# Rev1.net
KiCad netlist of a schematic drawn in EAGLE
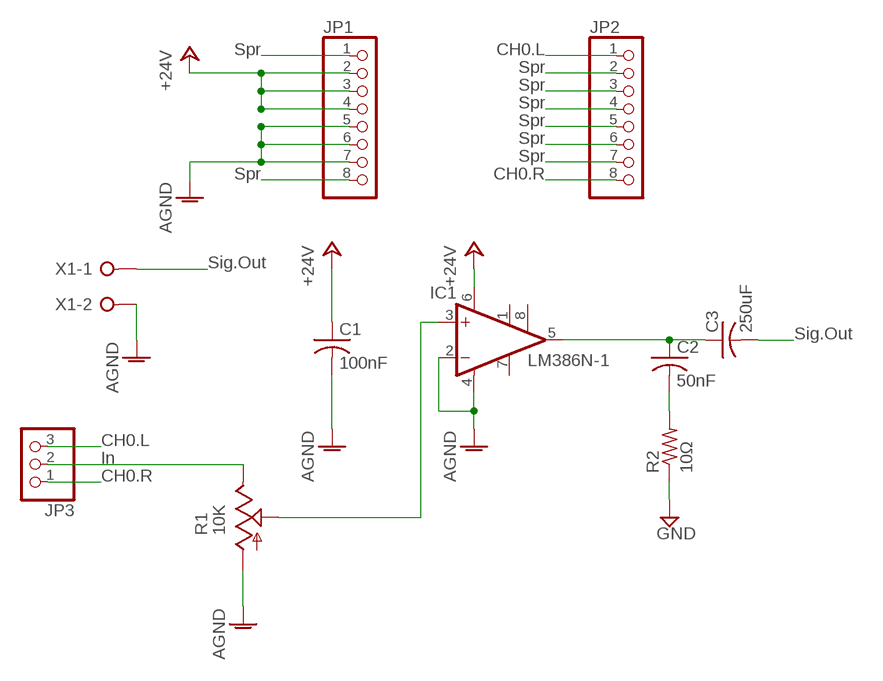
[diagram p0: schematic, sheet 1]

(export (version "E")
  (design (tool "Eeschema 10.0.6"))
  (components
    (comp (ref "C1")
      (value "100nF")
      (footprint "eagle-import:C075-032X103")
      (libsource (lib "eagle-import") (part "C-US075-032X103"))
    )
    (comp (ref "C2")
      (value "50nF")
      (footprint "eagle-import:C075-032X103")
      (libsource (lib "eagle-import") (part "C-US075-032X103"))
    )
    (comp (ref "C3")
      (value "250uF")
      (footprint "eagle-import:C025-050X050")
      (libsource (lib "eagle-import") (part "C-US025-050X050"))
    )
    (comp (ref "IC1")
      (value "LM386N-1")
      (footprint "eagle-import:DIL08")
      (libsource (lib "eagle-import") (part "LM386?-N1"))
    )
    (comp (ref "JP1")
      (value "PINHD-1X8")
      (footprint "eagle-import:1X08")
      (libsource (lib "eagle-import") (part "PINHD-1X8"))
    )
    (comp (ref "JP2")
      (value "PINHD-1X8")
      (footprint "eagle-import:1X08")
      (libsource (lib "eagle-import") (part "PINHD-1X8"))
    )
    (comp (ref "JP3")
      (value "PINHD-1X3")
      (footprint "eagle-import:1X03")
      (libsource (lib "eagle-import") (part "PINHD-1X3"))
    )
    (comp (ref "R1")
      (value "10K")
      (footprint "eagle-import:PT-10S")
      (libsource (lib "eagle-import") (part "TRIM_US-PT-10S"))
    )
    (comp (ref "R2")
      (value "10Ω")
      (footprint "eagle-import:0204_7")
      (libsource (lib "eagle-import") (part "R-US_0204/7"))
    )
    (comp (ref "X1")
      (value "W237-02P")
      (footprint "eagle-import:W237-132")
      (libsource (lib "eagle-import") (part "W237-02P"))
    )
  )
  (nets
    (net (code "1") (name "+24V") (class "Default")
      (node (ref "C1") (pin "1") (pinfunction "1_1") (pintype "passive"))
      (node (ref "IC1") (pin "6") (pinfunction "VS_6") (pintype "power_in"))
      (node (ref "JP1") (pin "2") (pinfunction "2_2") (pintype "passive"))
      (node (ref "JP1") (pin "3") (pinfunction "3_3") (pintype "passive"))
      (node (ref "JP1") (pin "4") (pinfunction "4_4") (pintype "passive"))
    )
    (net (code "2") (name "/CH0.L") (class "Default")
      (node (ref "JP2") (pin "1") (pinfunction "1_1") (pintype "passive"))
      (node (ref "JP3") (pin "3") (pinfunction "3_3") (pintype "passive"))
    )
    (net (code "3") (name "/CH0.R") (class "Default")
      (node (ref "JP2") (pin "8") (pinfunction "8_8") (pintype "passive"))
      (node (ref "JP3") (pin "1") (pinfunction "1_1") (pintype "passive"))
    )
    (net (code "4") (name "/SIGOUT") (class "Default")
      (node (ref "C3") (pin "2") (pinfunction "2_2") (pintype "passive"))
      (node (ref "X1") (pin "1") (pinfunction "KL_1") (pintype "passive"))
    )
    (net (code "5") (name "AGND") (class "Default")
      (node (ref "C1") (pin "2") (pinfunction "2_2") (pintype "passive"))
      (node (ref "IC1") (pin "2") (pinfunction "-IN_2") (pintype "input"))
      (node (ref "IC1") (pin "4") (pinfunction "GND_4") (pintype "power_in"))
      (node (ref "JP1") (pin "5") (pinfunction "5_5") (pintype "passive"))
      (node (ref "JP1") (pin "6") (pinfunction "6_6") (pintype "passive"))
      (node (ref "JP1") (pin "7") (pinfunction "7_7") (pintype "passive"))
      (node (ref "R1") (pin "A") (pinfunction "A_A") (pintype "passive"))
      (node (ref "X1") (pin "2") (pinfunction "KL_2") (pintype "passive"))
    )
    (net (code "6") (name "GND") (class "Default")
      (node (ref "R2") (pin "1") (pinfunction "1_1") (pintype "passive"))
    )
    (net (code "7") (name "Net-(C2-Pad2)") (class "Default")
      (node (ref "C2") (pin "2") (pinfunction "2_2") (pintype "passive"))
      (node (ref "R2") (pin "2") (pinfunction "2_2") (pintype "passive"))
    )
    (net (code "8") (name "Net-(IC1-+IN)") (class "Default")
      (node (ref "IC1") (pin "3") (pinfunction "+IN_3") (pintype "input"))
      (node (ref "R1") (pin "S") (pinfunction "S_S") (pintype "passive"))
    )
    (net (code "9") (name "Net-(IC1-OUT)") (class "Default")
      (node (ref "C2") (pin "1") (pinfunction "1_1") (pintype "passive"))
      (node (ref "C3") (pin "1") (pinfunction "1_1") (pintype "passive"))
      (node (ref "IC1") (pin "5") (pinfunction "OUT_5") (pintype "output"))
    )
    (net (code "10") (name "Net-(JP3-Pad2)") (class "Default")
      (node (ref "JP3") (pin "2") (pinfunction "2_2") (pintype "passive"))
      (node (ref "R1") (pin "E") (pinfunction "E_E") (pintype "passive"))
    )
    (net (code "11") (name "unconnected-(IC1-BYPASS-Pad7)") (class "Default")
      (node (ref "IC1") (pin "7") (pinfunction "BYPASS_7") (pintype "passive"))
    )
    (net (code "12") (name "unconnected-(IC1-GAIN-Pad1)") (class "Default")
      (node (ref "IC1") (pin "1") (pinfunction "GAIN_1") (pintype "passive"))
    )
    (net (code "13") (name "unconnected-(IC1-GAIN-Pad8)") (class "Default")
      (node (ref "IC1") (pin "8") (pinfunction "GAIN_8") (pintype "passive"))
    )
    (net (code "14") (name "unconnected-(JP1-Pad1)") (class "Default")
      (node (ref "JP1") (pin "1") (pinfunction "1_1") (pintype "passive"))
    )
    (net (code "15") (name "unconnected-(JP1-Pad8)") (class "Default")
      (node (ref "JP1") (pin "8") (pinfunction "8_8") (pintype "passive"))
    )
    (net (code "16") (name "unconnected-(JP2-Pad2)") (class "Default")
      (node (ref "JP2") (pin "2") (pinfunction "2_2") (pintype "passive"))
    )
    (net (code "17") (name "unconnected-(JP2-Pad3)") (class "Default")
      (node (ref "JP2") (pin "3") (pinfunction "3_3") (pintype "passive"))
    )
    (net (code "18") (name "unconnected-(JP2-Pad4)") (class "Default")
      (node (ref "JP2") (pin "4") (pinfunction "4_4") (pintype "passive"))
    )
    (net (code "19") (name "unconnected-(JP2-Pad5)") (class "Default")
      (node (ref "JP2") (pin "5") (pinfunction "5_5") (pintype "passive"))
    )
    (net (code "20") (name "unconnected-(JP2-Pad6)") (class "Default")
      (node (ref "JP2") (pin "6") (pinfunction "6_6") (pintype "passive"))
    )
    (net (code "21") (name "unconnected-(JP2-Pad7)") (class "Default")
      (node (ref "JP2") (pin "7") (pinfunction "7_7") (pintype "passive"))
    )
  )
)
